# 02-FPGA.net
KiCad netlist of a schematic drawn in Altium Designer
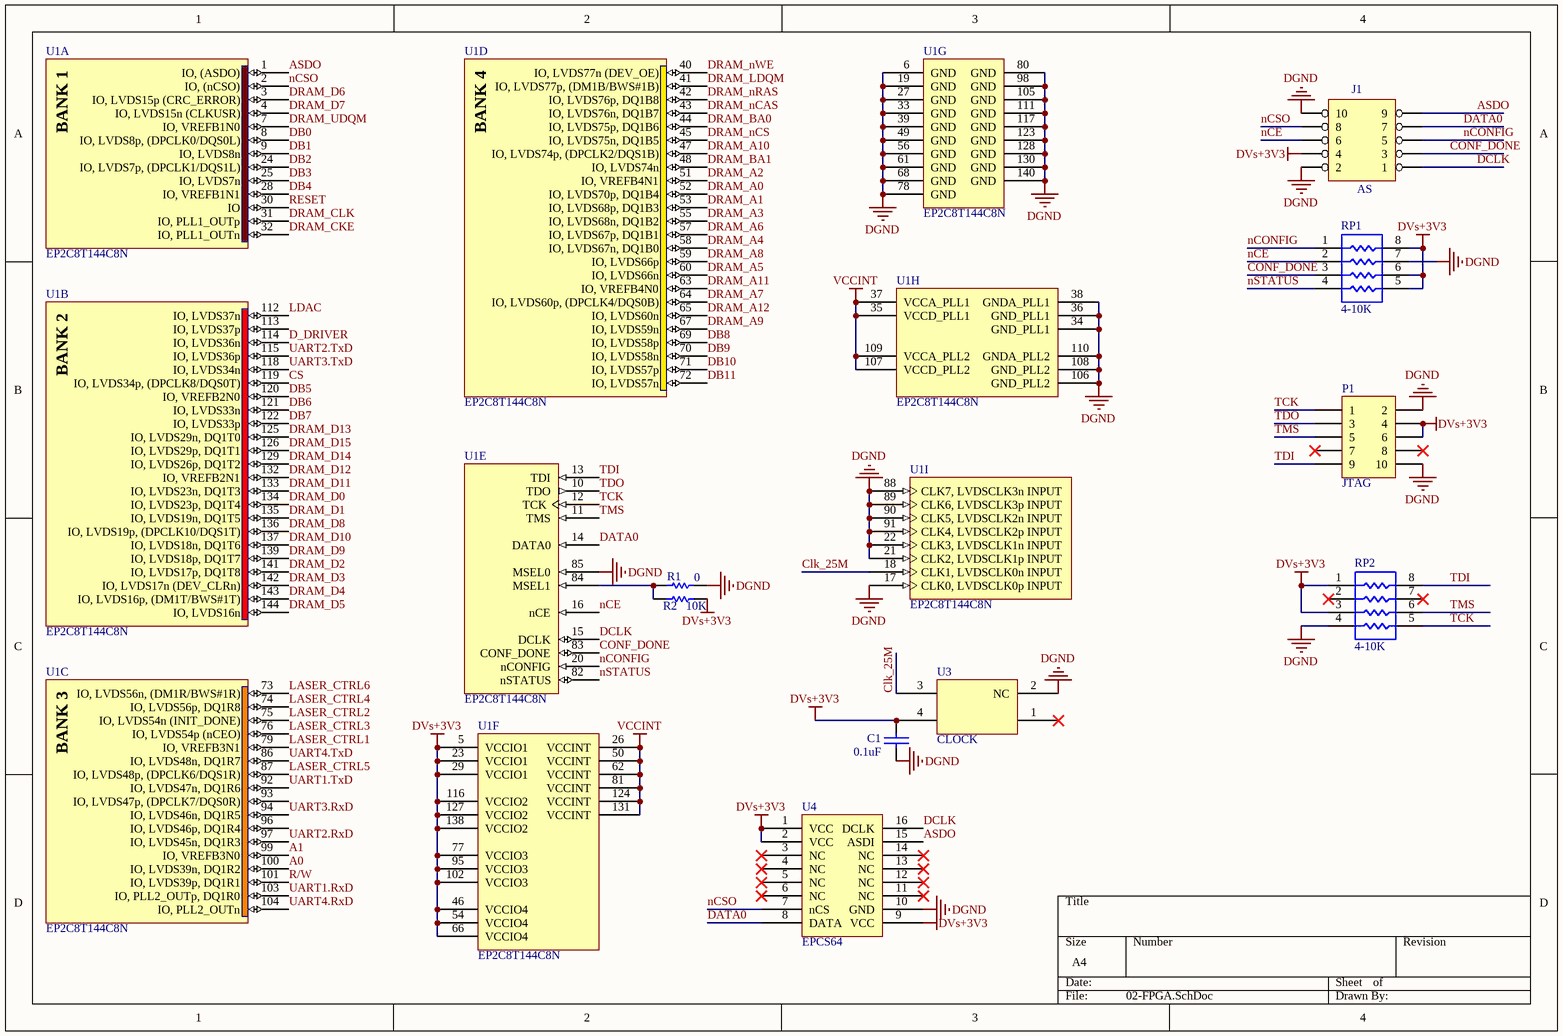
[diagram p0: 02-FPGA.SchDoc]

(export (version "E")
  (design (tool "Eeschema 10.0.6"))
  (components
    (comp (ref "C1")
      (value "0.1uF")
      (footprint "0805-X")
      (description "Capacitor")
      (libsource (lib "*") (part "CAP"))
    )
    (comp (ref "J1") (value "AS") (footprint "HDR2X5") (libsource (lib "*") (part "HEADER 5X2")))
    (comp (ref "P1")
      (value "JTAG")
      (footprint "HDR2X5")
      (description "Header, 5-Pin, Dual row")
      (fields (field (name "PUBLISHER") "Altium Limited"))
      (libsource (lib "Miscellaneous Connectors") (part "Header 5X2"))
    )
    (comp (ref "R1")
      (value "0")
      (footprint "0805-X")
      (description "Semiconductor Resistor")
      (fields (field (name "PUBLISHER") "Altium Limited"))
      (libsource (lib "Miscellaneous Devices") (part "Res Semi"))
    )
    (comp (ref "R2")
      (value "10K")
      (footprint "0805-X")
      (description "Semiconductor Resistor")
      (fields (field (name "PUBLISHER") "Altium Limited"))
      (libsource (lib "Miscellaneous Devices") (part "Res Semi"))
    )
    (comp (ref "RP1") (value "4-10K") (footprint "CRP4.1608") (libsource (lib "*") (part "RES-4")))
    (comp (ref "RP2") (value "4-10K") (footprint "CRP4.1608") (libsource (lib "*") (part "RES-4")))
    (comp (ref "U1")
      (value "EP2C8T144C8N")
      (footprint "F-QFP20X20-G144/N")
      (fields (field (name "PUBLISHER") "Altium Limited"))
      (libsource (lib "Altera Cyclone II") (part "EP2C8T144C8N"))
    )
    (comp (ref "U3") (value "CLOCK") (footprint "SMX_20MH") (libsource (lib "*") (part "CLOCK")))
    (comp (ref "U4")
      (value "EPCS64")
      (footprint "SO-G16/E6.9")
      (description "EPCS16 64 128")
      (libsource (lib "IC") (part "EPCS64"))
    )
  )
  (nets
    (net (code "1") (name "/A0") (class "Default")
      (node (ref "U1") (pin "100") (pinfunction "IO,_LVDS39n,_DQ1R2_100") (pintype "bidirectional"))
    )
    (net (code "2") (name "/A1") (class "Default")
      (node (ref "U1") (pin "99") (pinfunction "IO,_VREFB3N0_99") (pintype "bidirectional"))
    )
    (net (code "3") (name "/ASDO") (class "Default")
      (node (ref "J1") (pin "9") (pinfunction "9_9") (pintype "passive"))
      (node (ref "U1") (pin "1") (pinfunction "IO,_(ASDO)_1") (pintype "bidirectional"))
      (node (ref "U4") (pin "15") (pinfunction "ASDI_15") (pintype "passive"))
    )
    (net (code "4") (name "/CONF_DONE") (class "Default")
      (node (ref "J1") (pin "3") (pinfunction "3_3") (pintype "passive"))
      (node (ref "RP1") (pin "3") (pinfunction "3_3") (pintype "passive"))
      (node (ref "U1") (pin "83") (pinfunction "CONF_DONE_83") (pintype "bidirectional"))
    )
    (net (code "5") (name "/CS") (class "Default")
      (node (ref "U1") (pin "119") (pinfunction "IO,_LVDS34p,_(DPCLK8/DQS0T)_119") (pintype "bidirectional"))
    )
    (net (code "6") (name "/Clk_25M") (class "Default")
      (node (ref "U1") (pin "18") (pinfunction "CLK1,_LVDSCLK0n_INPUT_18") (pintype "input"))
      (node (ref "U3") (pin "3") (pintype "passive"))
    )
    (net (code "7") (name "/DATA0") (class "Default")
      (node (ref "J1") (pin "7") (pinfunction "7_7") (pintype "passive"))
      (node (ref "U1") (pin "14") (pinfunction "DATA0_14") (pintype "input"))
      (node (ref "U4") (pin "8") (pinfunction "DATA_8") (pintype "passive"))
    )
    (net (code "8") (name "/DB0") (class "Default")
      (node (ref "U1") (pin "8") (pinfunction "IO,_LVDS8p,_(DPCLK0/DQS0L)_8") (pintype "bidirectional"))
    )
    (net (code "9") (name "/DB1") (class "Default")
      (node (ref "U1") (pin "9") (pinfunction "IO,_LVDS8n_9") (pintype "bidirectional"))
    )
    (net (code "10") (name "/DB2") (class "Default")
      (node (ref "U1") (pin "24") (pinfunction "IO,_LVDS7p,_(DPCLK1/DQS1L)_24") (pintype "bidirectional"))
    )
    (net (code "11") (name "/DB3") (class "Default")
      (node (ref "U1") (pin "25") (pinfunction "IO,_LVDS7n_25") (pintype "bidirectional"))
    )
    (net (code "12") (name "/DB4") (class "Default")
      (node (ref "U1") (pin "28") (pinfunction "IO,_VREFB1N1_28") (pintype "bidirectional"))
    )
    (net (code "13") (name "/DB5") (class "Default")
      (node (ref "U1") (pin "120") (pinfunction "IO,_VREFB2N0_120") (pintype "bidirectional"))
    )
    (net (code "14") (name "/DB6") (class "Default")
      (node (ref "U1") (pin "121") (pinfunction "IO,_LVDS33n_121") (pintype "bidirectional"))
    )
    (net (code "15") (name "/DB7") (class "Default")
      (node (ref "U1") (pin "122") (pinfunction "IO,_LVDS33p_122") (pintype "bidirectional"))
    )
    (net (code "16") (name "/DB8") (class "Default")
      (node (ref "U1") (pin "69") (pinfunction "IO,_LVDS58p_69") (pintype "bidirectional"))
    )
    (net (code "17") (name "/DB9") (class "Default")
      (node (ref "U1") (pin "70") (pinfunction "IO,_LVDS58n_70") (pintype "bidirectional"))
    )
    (net (code "18") (name "/DB10") (class "Default")
      (node (ref "U1") (pin "71") (pinfunction "IO,_LVDS57p_71") (pintype "bidirectional"))
    )
    (net (code "19") (name "/DB11") (class "Default")
      (node (ref "U1") (pin "72") (pinfunction "IO,_LVDS57n_72") (pintype "bidirectional"))
    )
    (net (code "20") (name "/DCLK") (class "Default")
      (node (ref "J1") (pin "1") (pinfunction "1_1") (pintype "passive"))
      (node (ref "U1") (pin "15") (pinfunction "DCLK_15") (pintype "bidirectional"))
      (node (ref "U4") (pin "16") (pinfunction "DCLK_16") (pintype "passive"))
    )
    (net (code "21") (name "/DRAM_A0") (class "Default")
      (node (ref "U1") (pin "52") (pinfunction "IO,_LVDS70p,_DQ1B4_52") (pintype "bidirectional"))
    )
    (net (code "22") (name "/DRAM_A1") (class "Default")
      (node (ref "U1") (pin "53") (pinfunction "IO,_LVDS68p,_DQ1B3_53") (pintype "bidirectional"))
    )
    (net (code "23") (name "/DRAM_A2") (class "Default")
      (node (ref "U1") (pin "51") (pinfunction "IO,_VREFB4N1_51") (pintype "bidirectional"))
    )
    (net (code "24") (name "/DRAM_A3") (class "Default")
      (node (ref "U1") (pin "55") (pinfunction "IO,_LVDS68n,_DQ1B2_55") (pintype "bidirectional"))
    )
    (net (code "25") (name "/DRAM_A4") (class "Default")
      (node (ref "U1") (pin "58") (pinfunction "IO,_LVDS67n,_DQ1B0_58") (pintype "bidirectional"))
    )
    (net (code "26") (name "/DRAM_A5") (class "Default")
      (node (ref "U1") (pin "60") (pinfunction "IO,_LVDS66n_60") (pintype "bidirectional"))
    )
    (net (code "27") (name "/DRAM_A6") (class "Default")
      (node (ref "U1") (pin "57") (pinfunction "IO,_LVDS67p,_DQ1B1_57") (pintype "bidirectional"))
    )
    (net (code "28") (name "/DRAM_A7") (class "Default")
      (node (ref "U1") (pin "64") (pinfunction "IO,_LVDS60p,_(DPCLK4/DQS0B)_64") (pintype "bidirectional"))
    )
    (net (code "29") (name "/DRAM_A8") (class "Default")
      (node (ref "U1") (pin "59") (pinfunction "IO,_LVDS66p_59") (pintype "bidirectional"))
    )
    (net (code "30") (name "/DRAM_A9") (class "Default")
      (node (ref "U1") (pin "67") (pinfunction "IO,_LVDS59n_67") (pintype "bidirectional"))
    )
    (net (code "31") (name "/DRAM_A10") (class "Default")
      (node (ref "U1") (pin "47") (pinfunction "IO,_LVDS74p,_(DPCLK2/DQS1B)_47") (pintype "bidirectional"))
    )
    (net (code "32") (name "/DRAM_A11") (class "Default")
      (node (ref "U1") (pin "63") (pinfunction "IO,_VREFB4N0_63") (pintype "bidirectional"))
    )
    (net (code "33") (name "/DRAM_A12") (class "Default")
      (node (ref "U1") (pin "65") (pinfunction "IO,_LVDS60n_65") (pintype "bidirectional"))
    )
    (net (code "34") (name "/DRAM_BA0") (class "Default")
      (node (ref "U1") (pin "44") (pinfunction "IO,_LVDS75p,_DQ1B6_44") (pintype "bidirectional"))
    )
    (net (code "35") (name "/DRAM_BA1") (class "Default")
      (node (ref "U1") (pin "48") (pinfunction "IO,_LVDS74n_48") (pintype "bidirectional"))
    )
    (net (code "36") (name "/DRAM_CKE") (class "Default")
      (node (ref "U1") (pin "32") (pinfunction "IO,_PLL1_OUTn_32") (pintype "bidirectional"))
    )
    (net (code "37") (name "/DRAM_CLK") (class "Default")
      (node (ref "U1") (pin "31") (pinfunction "IO,_PLL1_OUTp_31") (pintype "bidirectional"))
    )
    (net (code "38") (name "/DRAM_D0") (class "Default")
      (node (ref "U1") (pin "134") (pinfunction "IO,_LVDS23p,_DQ1T4_134") (pintype "bidirectional"))
    )
    (net (code "39") (name "/DRAM_D1") (class "Default")
      (node (ref "U1") (pin "135") (pinfunction "IO,_LVDS19n,_DQ1T5_135") (pintype "bidirectional"))
    )
    (net (code "40") (name "/DRAM_D2") (class "Default")
      (node (ref "U1") (pin "141") (pinfunction "IO,_LVDS17p,_DQ1T8_141") (pintype "bidirectional"))
    )
    (net (code "41") (name "/DRAM_D3") (class "Default")
      (node (ref "U1") (pin "142") (pinfunction "IO,_LVDS17n_(DEV_CLRn)_142") (pintype "bidirectional"))
    )
    (net (code "42") (name "/DRAM_D4") (class "Default")
      (node (ref "U1") (pin "143") (pinfunction "IO,_LVDS16p,_(DM1T/BWS#1T)_143") (pintype "bidirectional"))
    )
    (net (code "43") (name "/DRAM_D5") (class "Default")
      (node (ref "U1") (pin "144") (pinfunction "IO,_LVDS16n_144") (pintype "bidirectional"))
    )
    (net (code "44") (name "/DRAM_D6") (class "Default")
      (node (ref "U1") (pin "3") (pinfunction "IO,_LVDS15p_(CRC_ERROR)_3") (pintype "bidirectional"))
    )
    (net (code "45") (name "/DRAM_D7") (class "Default")
      (node (ref "U1") (pin "4") (pinfunction "IO,_LVDS15n_(CLKUSR)_4") (pintype "bidirectional"))
    )
    (net (code "46") (name "/DRAM_D8") (class "Default")
      (node (ref "U1") (pin "136") (pinfunction "IO,_LVDS19p,_(DPCLK10/DQS1T)_136") (pintype "bidirectional"))
    )
    (net (code "47") (name "/DRAM_D9") (class "Default")
      (node (ref "U1") (pin "139") (pinfunction "IO,_LVDS18p,_DQ1T7_139") (pintype "bidirectional"))
    )
    (net (code "48") (name "/DRAM_D10") (class "Default")
      (node (ref "U1") (pin "137") (pinfunction "IO,_LVDS18n,_DQ1T6_137") (pintype "bidirectional"))
    )
    (net (code "49") (name "/DRAM_D11") (class "Default")
      (node (ref "U1") (pin "133") (pinfunction "IO,_LVDS23n,_DQ1T3_133") (pintype "bidirectional"))
    )
    (net (code "50") (name "/DRAM_D12") (class "Default")
      (node (ref "U1") (pin "132") (pinfunction "IO,_VREFB2N1_132") (pintype "bidirectional"))
    )
    (net (code "51") (name "/DRAM_D13") (class "Default")
      (node (ref "U1") (pin "125") (pinfunction "IO,_LVDS29n,_DQ1T0_125") (pintype "bidirectional"))
    )
    (net (code "52") (name "/DRAM_D14") (class "Default")
      (node (ref "U1") (pin "129") (pinfunction "IO,_LVDS26p,_DQ1T2_129") (pintype "bidirectional"))
    )
    (net (code "53") (name "/DRAM_D15") (class "Default")
      (node (ref "U1") (pin "126") (pinfunction "IO,_LVDS29p,_DQ1T1_126") (pintype "bidirectional"))
    )
    (net (code "54") (name "/DRAM_LDQM") (class "Default")
      (node (ref "U1") (pin "41") (pinfunction "IO,_LVDS77p,_(DM1B/BWS#1B)_41") (pintype "bidirectional"))
    )
    (net (code "55") (name "/DRAM_UDQM") (class "Default")
      (node (ref "U1") (pin "7") (pinfunction "IO,_VREFB1N0_7") (pintype "bidirectional"))
    )
    (net (code "56") (name "/DRAM_nCAS") (class "Default")
      (node (ref "U1") (pin "43") (pinfunction "IO,_LVDS76n,_DQ1B7_43") (pintype "bidirectional"))
    )
    (net (code "57") (name "/DRAM_nCS") (class "Default")
      (node (ref "U1") (pin "45") (pinfunction "IO,_LVDS75n,_DQ1B5_45") (pintype "bidirectional"))
    )
    (net (code "58") (name "/DRAM_nRAS") (class "Default")
      (node (ref "U1") (pin "42") (pinfunction "IO,_LVDS76p,_DQ1B8_42") (pintype "bidirectional"))
    )
    (net (code "59") (name "/DRAM_nWE") (class "Default")
      (node (ref "U1") (pin "40") (pinfunction "IO,_LVDS77n_(DEV_OE)_40") (pintype "bidirectional"))
    )
    (net (code "60") (name "/D_DRIVER") (class "Default")
      (node (ref "U1") (pin "114") (pinfunction "IO,_LVDS36n_114") (pintype "bidirectional"))
    )
    (net (code "61") (name "/LASER_CTRL1") (class "Default")
      (node (ref "U1") (pin "79") (pinfunction "IO,_VREFB3N1_79") (pintype "bidirectional"))
    )
    (net (code "62") (name "/LASER_CTRL2") (class "Default")
      (node (ref "U1") (pin "75") (pinfunction "IO,_LVDS54n_(INIT_DONE)_75") (pintype "bidirectional"))
    )
    (net (code "63") (name "/LASER_CTRL3") (class "Default")
      (node (ref "U1") (pin "76") (pinfunction "IO,_LVDS54p_(nCEO)_76") (pintype "bidirectional"))
    )
    (net (code "64") (name "/LASER_CTRL4") (class "Default")
      (node (ref "U1") (pin "74") (pinfunction "IO,_LVDS56p,_DQ1R8_74") (pintype "bidirectional"))
    )
    (net (code "65") (name "/LASER_CTRL5") (class "Default")
      (node (ref "U1") (pin "87") (pinfunction "IO,_LVDS48p,_(DPCLK6/DQS1R)_87") (pintype "bidirectional"))
    )
    (net (code "66") (name "/LASER_CTRL6") (class "Default")
      (node (ref "U1") (pin "73") (pinfunction "IO,_LVDS56n,_(DM1R/BWS#1R)_73") (pintype "bidirectional"))
    )
    (net (code "67") (name "/LDAC") (class "Default")
      (node (ref "U1") (pin "112") (pinfunction "IO,_LVDS37n_112") (pintype "bidirectional"))
    )
    (net (code "68") (name "/RESET") (class "Default")
      (node (ref "U1") (pin "30") (pinfunction "IO_30") (pintype "bidirectional"))
    )
    (net (code "69") (name "/R{slash}W") (class "Default")
      (node (ref "U1") (pin "101") (pinfunction "IO,_LVDS39p,_DQ1R1_101") (pintype "bidirectional"))
    )
    (net (code "70") (name "/TCK") (class "Default")
      (node (ref "P1") (pin "1") (pinfunction "1_1") (pintype "passive"))
      (node (ref "RP2") (pin "5") (pinfunction "5_5") (pintype "passive"))
      (node (ref "U1") (pin "12") (pinfunction "TCK_12") (pintype "input"))
    )
    (net (code "71") (name "/TDI") (class "Default")
      (node (ref "P1") (pin "9") (pinfunction "9_9") (pintype "passive"))
      (node (ref "RP2") (pin "8") (pinfunction "8_8") (pintype "passive"))
      (node (ref "U1") (pin "13") (pinfunction "TDI_13") (pintype "input"))
    )
    (net (code "72") (name "/TDO") (class "Default")
      (node (ref "P1") (pin "3") (pinfunction "3_3") (pintype "passive"))
      (node (ref "U1") (pin "10") (pinfunction "TDO_10") (pintype "output"))
    )
    (net (code "73") (name "/TMS") (class "Default")
      (node (ref "P1") (pin "5") (pinfunction "5_5") (pintype "passive"))
      (node (ref "RP2") (pin "6") (pinfunction "6_6") (pintype "passive"))
      (node (ref "U1") (pin "11") (pinfunction "TMS_11") (pintype "input"))
    )
    (net (code "74") (name "/UART1.RxD") (class "Default")
      (node (ref "U1") (pin "103") (pinfunction "IO,_PLL2_OUTp,_DQ1R0_103") (pintype "bidirectional"))
    )
    (net (code "75") (name "/UART1.TxD") (class "Default")
      (node (ref "U1") (pin "92") (pinfunction "IO,_LVDS47n,_DQ1R6_92") (pintype "bidirectional"))
    )
    (net (code "76") (name "/UART2.RxD") (class "Default")
      (node (ref "U1") (pin "97") (pinfunction "IO,_LVDS45n,_DQ1R3_97") (pintype "bidirectional"))
    )
    (net (code "77") (name "/UART2.TxD") (class "Default")
      (node (ref "U1") (pin "115") (pinfunction "IO,_LVDS36p_115") (pintype "bidirectional"))
    )
    (net (code "78") (name "/UART3.RxD") (class "Default")
      (node (ref "U1") (pin "94") (pinfunction "IO,_LVDS46n,_DQ1R5_94") (pintype "bidirectional"))
    )
    (net (code "79") (name "/UART3.TxD") (class "Default")
      (node (ref "U1") (pin "118") (pinfunction "IO,_LVDS34n_118") (pintype "bidirectional"))
    )
    (net (code "80") (name "/UART4.RxD") (class "Default")
      (node (ref "U1") (pin "104") (pinfunction "IO,_PLL2_OUTn_104") (pintype "bidirectional"))
    )
    (net (code "81") (name "/UART4.TxD") (class "Default")
      (node (ref "U1") (pin "86") (pinfunction "IO,_LVDS48n,_DQ1R7_86") (pintype "bidirectional"))
    )
    (net (code "82") (name "/nCE") (class "Default")
      (node (ref "J1") (pin "6") (pinfunction "6_6") (pintype "passive"))
      (node (ref "RP1") (pin "2") (pinfunction "2_2") (pintype "passive"))
      (node (ref "U1") (pin "16") (pinfunction "nCE_16") (pintype "input"))
    )
    (net (code "83") (name "/nCONFIG") (class "Default")
      (node (ref "J1") (pin "5") (pinfunction "5_5") (pintype "passive"))
      (node (ref "RP1") (pin "1") (pinfunction "1_1") (pintype "passive"))
      (node (ref "U1") (pin "20") (pinfunction "nCONFIG_20") (pintype "input"))
    )
    (net (code "84") (name "/nCSO") (class "Default")
      (node (ref "J1") (pin "8") (pinfunction "8_8") (pintype "passive"))
      (node (ref "U1") (pin "2") (pinfunction "IO,_(nCSO)_2") (pintype "bidirectional"))
      (node (ref "U4") (pin "7") (pinfunction "nCS_7") (pintype "passive"))
    )
    (net (code "85") (name "/nSTATUS") (class "Default")
      (node (ref "RP1") (pin "4") (pinfunction "4_4") (pintype "passive"))
      (node (ref "U1") (pin "82") (pinfunction "nSTATUS_82") (pintype "bidirectional"))
    )
    (net (code "86") (name "DGND") (class "Default")
      (node (ref "C1") (pin "1") (pinfunction "1_1") (pintype "passive"))
      (node (ref "J1") (pin "10") (pinfunction "10_10") (pintype "passive"))
      (node (ref "J1") (pin "2") (pinfunction "2_2") (pintype "passive"))
      (node (ref "P1") (pin "10") (pinfunction "10_10") (pintype "passive"))
      (node (ref "P1") (pin "2") (pinfunction "2_2") (pintype "passive"))
      (node (ref "R1") (pin "2") (pinfunction "2_2") (pintype "passive"))
      (node (ref "RP1") (pin "7") (pinfunction "7_7") (pintype "passive"))
      (node (ref "RP2") (pin "4") (pinfunction "4_4") (pintype "passive"))
      (node (ref "U1") (pin "105") (pinfunction "GND_105") (pintype "power_in"))
      (node (ref "U1") (pin "106") (pinfunction "GND_PLL2_106") (pintype "power_in"))
      (node (ref "U1") (pin "108") (pinfunction "GND_PLL2_108") (pintype "power_in"))
      (node (ref "U1") (pin "110") (pinfunction "GNDA_PLL2_110") (pintype "power_in"))
      (node (ref "U1") (pin "111") (pinfunction "GND_111") (pintype "power_in"))
      (node (ref "U1") (pin "117") (pinfunction "GND_117") (pintype "power_in"))
      (node (ref "U1") (pin "123") (pinfunction "GND_123") (pintype "power_in"))
      (node (ref "U1") (pin "128") (pinfunction "GND_128") (pintype "power_in"))
      (node (ref "U1") (pin "130") (pinfunction "GND_130") (pintype "power_in"))
      (node (ref "U1") (pin "140") (pinfunction "GND_140") (pintype "power_in"))
      (node (ref "U1") (pin "17") (pinfunction "CLK0,_LVDSCLK0p_INPUT_17") (pintype "input"))
      (node (ref "U1") (pin "19") (pinfunction "GND_19") (pintype "power_in"))
      (node (ref "U1") (pin "21") (pinfunction "CLK2,_LVDSCLK1p_INPUT_21") (pintype "input"))
      (node (ref "U1") (pin "22") (pinfunction "CLK3,_LVDSCLK1n_INPUT_22") (pintype "input"))
      (node (ref "U1") (pin "27") (pinfunction "GND_27") (pintype "power_in"))
      (node (ref "U1") (pin "33") (pinfunction "GND_33") (pintype "power_in"))
      (node (ref "U1") (pin "34") (pinfunction "GND_PLL1_34") (pintype "power_in"))
      (node (ref "U1") (pin "36") (pinfunction "GND_PLL1_36") (pintype "power_in"))
      (node (ref "U1") (pin "38") (pinfunction "GNDA_PLL1_38") (pintype "power_in"))
      (node (ref "U1") (pin "39") (pinfunction "GND_39") (pintype "power_in"))
      (node (ref "U1") (pin "49") (pinfunction "GND_49") (pintype "power_in"))
      (node (ref "U1") (pin "56") (pinfunction "GND_56") (pintype "power_in"))
      (node (ref "U1") (pin "6") (pinfunction "GND_6") (pintype "power_in"))
      (node (ref "U1") (pin "61") (pinfunction "GND_61") (pintype "power_in"))
      (node (ref "U1") (pin "68") (pinfunction "GND_68") (pintype "power_in"))
      (node (ref "U1") (pin "78") (pinfunction "GND_78") (pintype "power_in"))
      (node (ref "U1") (pin "80") (pinfunction "GND_80") (pintype "power_in"))
      (node (ref "U1") (pin "85") (pinfunction "MSEL0_85") (pintype "input"))
      (node (ref "U1") (pin "88") (pinfunction "CLK7,_LVDSCLK3n_INPUT_88") (pintype "input"))
      (node (ref "U1") (pin "89") (pinfunction "CLK6,_LVDSCLK3p_INPUT_89") (pintype "input"))
      (node (ref "U1") (pin "90") (pinfunction "CLK5,_LVDSCLK2n_INPUT_90") (pintype "input"))
      (node (ref "U1") (pin "91") (pinfunction "CLK4,_LVDSCLK2p_INPUT_91") (pintype "input"))
      (node (ref "U1") (pin "98") (pinfunction "GND_98") (pintype "power_in"))
      (node (ref "U3") (pin "2") (pinfunction "NC_2") (pintype "passive"))
      (node (ref "U4") (pin "10") (pinfunction "GND_10") (pintype "passive"))
    )
    (net (code "87") (name "DVs+3V3") (class "Default")
      (node (ref "C1") (pin "2") (pinfunction "2_2") (pintype "passive"))
      (node (ref "J1") (pin "4") (pinfunction "4_4") (pintype "passive"))
      (node (ref "P1") (pin "4") (pinfunction "4_4") (pintype "passive"))
      (node (ref "P1") (pin "6") (pinfunction "6_6") (pintype "passive"))
      (node (ref "R2") (pin "2") (pinfunction "2_2") (pintype "passive"))
      (node (ref "RP1") (pin "5") (pinfunction "5_5") (pintype "passive"))
      (node (ref "RP1") (pin "6") (pinfunction "6_6") (pintype "passive"))
      (node (ref "RP1") (pin "8") (pinfunction "8_8") (pintype "passive"))
      (node (ref "RP2") (pin "1") (pinfunction "1_1") (pintype "passive"))
      (node (ref "RP2") (pin "3") (pinfunction "3_3") (pintype "passive"))
      (node (ref "U1") (pin "102") (pinfunction "VCCIO3_102") (pintype "power_in"))
      (node (ref "U1") (pin "116") (pinfunction "VCCIO2_116") (pintype "power_in"))
      (node (ref "U1") (pin "127") (pinfunction "VCCIO2_127") (pintype "power_in"))
      (node (ref "U1") (pin "138") (pinfunction "VCCIO2_138") (pintype "power_in"))
      (node (ref "U1") (pin "23") (pinfunction "VCCIO1_23") (pintype "power_in"))
      (node (ref "U1") (pin "29") (pinfunction "VCCIO1_29") (pintype "power_in"))
      (node (ref "U1") (pin "46") (pinfunction "VCCIO4_46") (pintype "power_in"))
      (node (ref "U1") (pin "5") (pinfunction "VCCIO1_5") (pintype "power_in"))
      (node (ref "U1") (pin "54") (pinfunction "VCCIO4_54") (pintype "power_in"))
      (node (ref "U1") (pin "66") (pinfunction "VCCIO4_66") (pintype "power_in"))
      (node (ref "U1") (pin "77") (pinfunction "VCCIO3_77") (pintype "power_in"))
      (node (ref "U1") (pin "95") (pinfunction "VCCIO3_95") (pintype "power_in"))
      (node (ref "U3") (pin "4") (pintype "passive"))
      (node (ref "U4") (pin "1") (pinfunction "VCC_1") (pintype "passive"))
      (node (ref "U4") (pin "2") (pinfunction "VCC_2") (pintype "passive"))
      (node (ref "U4") (pin "9") (pinfunction "VCC_9") (pintype "passive"))
    )
    (net (code "88") (name "Net-(U1E-MSEL1)") (class "Default")
      (node (ref "R1") (pin "1") (pinfunction "1_1") (pintype "passive"))
      (node (ref "R2") (pin "1") (pinfunction "1_1") (pintype "passive"))
      (node (ref "U1") (pin "84") (pinfunction "MSEL1_84") (pintype "input"))
    )
    (net (code "89") (name "VCCINT") (class "Default")
      (node (ref "U1") (pin "107") (pinfunction "VCCD_PLL2_107") (pintype "power_in"))
      (node (ref "U1") (pin "109") (pinfunction "VCCA_PLL2_109") (pintype "power_in"))
      (node (ref "U1") (pin "124") (pinfunction "VCCINT_124") (pintype "power_in"))
      (node (ref "U1") (pin "131") (pinfunction "VCCINT_131") (pintype "power_in"))
      (node (ref "U1") (pin "26") (pinfunction "VCCINT_26") (pintype "power_in"))
      (node (ref "U1") (pin "35") (pinfunction "VCCD_PLL1_35") (pintype "power_in"))
      (node (ref "U1") (pin "37") (pinfunction "VCCA_PLL1_37") (pintype "power_in"))
      (node (ref "U1") (pin "50") (pinfunction "VCCINT_50") (pintype "power_in"))
      (node (ref "U1") (pin "62") (pinfunction "VCCINT_62") (pintype "power_in"))
      (node (ref "U1") (pin "81") (pinfunction "VCCINT_81") (pintype "power_in"))
    )
    (net (code "90") (name "unconnected-(P1-Pad7)") (class "Default")
      (node (ref "P1") (pin "7") (pinfunction "7_7") (pintype "passive+no_connect"))
    )
    (net (code "91") (name "unconnected-(P1-Pad8)") (class "Default")
      (node (ref "P1") (pin "8") (pinfunction "8_8") (pintype "passive+no_connect"))
    )
    (net (code "92") (name "unconnected-(RP2-Pad2)") (class "Default")
      (node (ref "RP2") (pin "2") (pinfunction "2_2") (pintype "passive+no_connect"))
    )
    (net (code "93") (name "unconnected-(RP2-Pad7)") (class "Default")
      (node (ref "RP2") (pin "7") (pinfunction "7_7") (pintype "passive+no_connect"))
    )
    (net (code "94") (name "unconnected-(U1B-IO,_LVDS37p-Pad113)") (class "Default")
      (node (ref "U1") (pin "113") (pinfunction "IO,_LVDS37p_113") (pintype "bidirectional"))
    )
    (net (code "95") (name "unconnected-(U1C-IO,_LVDS46p,_DQ1R4-Pad96)") (class "Default")
      (node (ref "U1") (pin "96") (pinfunction "IO,_LVDS46p,_DQ1R4_96") (pintype "bidirectional"))
    )
    (net (code "96") (name "unconnected-(U1C-IO,_LVDS47p,_(DPCLK7{slash}DQS0R)-Pad93)") (class "Default")
      (node (ref "U1") (pin "93") (pinfunction "IO,_LVDS47p,_(DPCLK7/DQS0R)_93") (pintype "bidirectional"))
    )
    (net (code "97") (name "unconnected-(U3-Pad1)") (class "Default")
      (node (ref "U3") (pin "1") (pintype "passive+no_connect"))
    )
    (net (code "98") (name "unconnected-(U4-NC-Pad3)") (class "Default")
      (node (ref "U4") (pin "3") (pinfunction "NC_3") (pintype "passive+no_connect"))
    )
    (net (code "99") (name "unconnected-(U4-NC-Pad4)") (class "Default")
      (node (ref "U4") (pin "4") (pinfunction "NC_4") (pintype "passive+no_connect"))
    )
    (net (code "100") (name "unconnected-(U4-NC-Pad5)") (class "Default")
      (node (ref "U4") (pin "5") (pinfunction "NC_5") (pintype "passive+no_connect"))
    )
    (net (code "101") (name "unconnected-(U4-NC-Pad6)") (class "Default")
      (node (ref "U4") (pin "6") (pinfunction "NC_6") (pintype "passive+no_connect"))
    )
    (net (code "102") (name "unconnected-(U4-NC-Pad11)") (class "Default")
      (node (ref "U4") (pin "11") (pinfunction "NC_11") (pintype "passive+no_connect"))
    )
    (net (code "103") (name "unconnected-(U4-NC-Pad12)") (class "Default")
      (node (ref "U4") (pin "12") (pinfunction "NC_12") (pintype "passive+no_connect"))
    )
    (net (code "104") (name "unconnected-(U4-NC-Pad13)") (class "Default")
      (node (ref "U4") (pin "13") (pinfunction "NC_13") (pintype "passive+no_connect"))
    )
    (net (code "105") (name "unconnected-(U4-NC-Pad14)") (class "Default")
      (node (ref "U4") (pin "14") (pinfunction "NC_14") (pintype "passive+no_connect"))
    )
  )
)
